# led4.net
KiCad netlist of a schematic drawn in Altium Designer
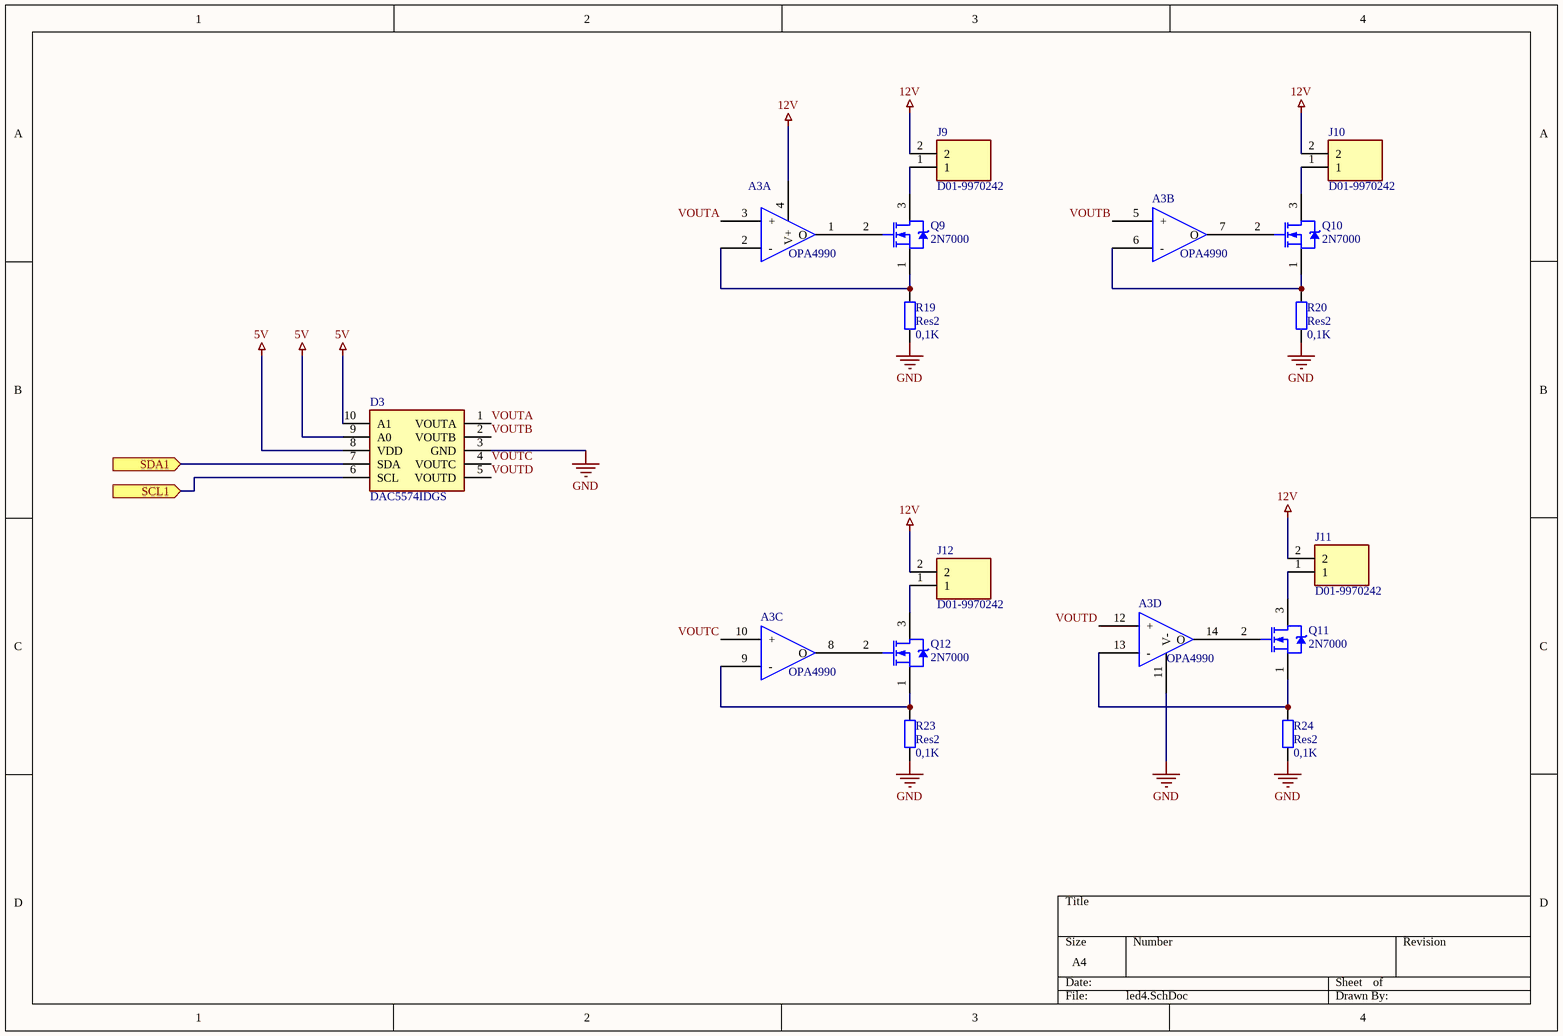
[diagram p0: led4.SchDoc]

(export (version "E")
  (design (tool "Eeschema 10.0.6"))
  (components
    (comp (ref "A3")
      (value "OPA4990")
      (footprint "SOIC127P600X175-14N")
      (libsource (lib "Kalibracija") (part "OPA4990"))
    )
    (comp (ref "D3")
      (value "DAC5574IDGS")
      (footprint "SOP50P490X110-10N")
      (description "Integrated Circuit")
      (fields
        (field (name "MOUSER PART NUMBER") "595-DAC5574IDGS")
        (field (name "RS PART NUMBER") "6621533P")
      )
      (libsource (lib "*") (part "DAC5574IDGS"))
    )
    (comp (ref "J9")
      (value "D01-9970242")
      (footprint "HDR1X2")
      (description "Connector")
      (fields (field (name "MOUSER PART NUMBER") "855-D01-9970242"))
      (libsource (lib "SamacSys2") (part "D01-9970242"))
    )
    (comp (ref "J10")
      (value "D01-9970242")
      (footprint "HDR1X2")
      (description "Connector")
      (fields (field (name "MOUSER PART NUMBER") "855-D01-9970242"))
      (libsource (lib "SamacSys2") (part "D01-9970242"))
    )
    (comp (ref "J11")
      (value "D01-9970242")
      (footprint "HDR1X2")
      (description "Connector")
      (fields (field (name "MOUSER PART NUMBER") "855-D01-9970242"))
      (libsource (lib "SamacSys2") (part "D01-9970242"))
    )
    (comp (ref "J12")
      (value "D01-9970242")
      (footprint "HDR1X2")
      (description "Connector")
      (fields (field (name "MOUSER PART NUMBER") "855-D01-9970242"))
      (libsource (lib "SamacSys2") (part "D01-9970242"))
    )
    (comp (ref "Q9")
      (value "2N7000")
      (footprint "ONSC-TO-92-3-29-11")
      (description "Small Signal MOSFET, 200 mA, 60 V, N-Channel, 3-Pin TO-92, Bulk Box")
      (fields (field (name "MANUFACTURER") "On Semiconductor"))
      (libsource (lib "Components - 24.04.20 - 07.58") (part "CMP-1058-00936-1"))
    )
    (comp (ref "Q10")
      (value "2N7000")
      (footprint "ONSC-TO-92-3-29-11")
      (description "Small Signal MOSFET, 200 mA, 60 V, N-Channel, 3-Pin TO-92, Bulk Box")
      (fields (field (name "MANUFACTURER") "On Semiconductor"))
      (libsource (lib "Components - 24.04.20 - 07.58") (part "CMP-1058-00936-1"))
    )
    (comp (ref "Q11")
      (value "2N7000")
      (footprint "ONSC-TO-92-3-29-11")
      (description "Small Signal MOSFET, 200 mA, 60 V, N-Channel, 3-Pin TO-92, Bulk Box")
      (fields (field (name "MANUFACTURER") "On Semiconductor"))
      (libsource (lib "Components - 24.04.20 - 07.58") (part "CMP-1058-00936-1"))
    )
    (comp (ref "Q12")
      (value "2N7000")
      (footprint "ONSC-TO-92-3-29-11")
      (description "Small Signal MOSFET, 200 mA, 60 V, N-Channel, 3-Pin TO-92, Bulk Box")
      (fields (field (name "MANUFACTURER") "On Semiconductor"))
      (libsource (lib "Components - 24.04.20 - 07.58") (part "CMP-1058-00936-1"))
    )
    (comp (ref "R19")
      (value "Res2")
      (footprint "C1210")
      (description "Resistor")
      (fields (field (name "ALTIUM_VALUE") "0,1K") (field (name "PUBLISHER") "Altium Limited"))
      (libsource (lib "Miscellaneous Devices") (part "Res2"))
    )
    (comp (ref "R20")
      (value "Res2")
      (footprint "C1210")
      (description "Resistor")
      (fields (field (name "ALTIUM_VALUE") "0,1K") (field (name "PUBLISHER") "Altium Limited"))
      (libsource (lib "Miscellaneous Devices") (part "Res2"))
    )
    (comp (ref "R23")
      (value "Res2")
      (footprint "C1210")
      (description "Resistor")
      (fields (field (name "ALTIUM_VALUE") "0,1K") (field (name "PUBLISHER") "Altium Limited"))
      (libsource (lib "Miscellaneous Devices") (part "Res2"))
    )
    (comp (ref "R24")
      (value "Res2")
      (footprint "C1210")
      (description "Resistor")
      (fields (field (name "ALTIUM_VALUE") "0,1K") (field (name "PUBLISHER") "Altium Limited"))
      (libsource (lib "Miscellaneous Devices") (part "Res2"))
    )
  )
  (nets
    (net (code "1") (name "/SCL1") (class "Default")
      (node (ref "D3") (pin "6") (pinfunction "SCL_6") (pintype "passive"))
    )
    (net (code "2") (name "/SDA1") (class "Default")
      (node (ref "D3") (pin "7") (pinfunction "SDA_7") (pintype "passive"))
    )
    (net (code "3") (name "/VOUTA") (class "Default")
      (node (ref "A3") (pin "3") (pinfunction "+_3") (pintype "passive"))
      (node (ref "D3") (pin "1") (pinfunction "VOUTA_1") (pintype "passive"))
    )
    (net (code "4") (name "/VOUTB") (class "Default")
      (node (ref "A3") (pin "5") (pinfunction "+_5") (pintype "passive"))
      (node (ref "D3") (pin "2") (pinfunction "VOUTB_2") (pintype "passive"))
    )
    (net (code "5") (name "/VOUTC") (class "Default")
      (node (ref "A3") (pin "10") (pinfunction "+_10") (pintype "passive"))
      (node (ref "D3") (pin "4") (pinfunction "VOUTC_4") (pintype "passive"))
    )
    (net (code "6") (name "/VOUTD") (class "Default")
      (node (ref "A3") (pin "12") (pinfunction "+_12") (pintype "passive"))
      (node (ref "D3") (pin "5") (pinfunction "VOUTD_5") (pintype "passive"))
    )
    (net (code "7") (name "5V") (class "Default")
      (node (ref "D3") (pin "10") (pinfunction "A1_10") (pintype "passive"))
      (node (ref "D3") (pin "8") (pinfunction "VDD_8") (pintype "passive"))
      (node (ref "D3") (pin "9") (pinfunction "A0_9") (pintype "passive"))
    )
    (net (code "8") (name "12V") (class "Default")
      (node (ref "A3") (pin "4") (pinfunction "V+_4") (pintype "power_in"))
      (node (ref "J10") (pin "2") (pinfunction "2_2") (pintype "passive"))
      (node (ref "J11") (pin "2") (pinfunction "2_2") (pintype "passive"))
      (node (ref "J12") (pin "2") (pinfunction "2_2") (pintype "passive"))
      (node (ref "J9") (pin "2") (pinfunction "2_2") (pintype "passive"))
    )
    (net (code "9") (name "GND") (class "Default")
      (node (ref "A3") (pin "11") (pinfunction "V-_11") (pintype "power_in"))
      (node (ref "D3") (pin "3") (pinfunction "GND_3") (pintype "passive"))
      (node (ref "R19") (pin "1") (pinfunction "1_1") (pintype "passive"))
      (node (ref "R20") (pin "1") (pinfunction "1_1") (pintype "passive"))
      (node (ref "R23") (pin "1") (pinfunction "1_1") (pintype "passive"))
      (node (ref "R24") (pin "1") (pinfunction "1_1") (pintype "passive"))
    )
    (net (code "10") (name "Net-(A3A--)") (class "Default")
      (node (ref "A3") (pin "2") (pinfunction "-_2") (pintype "passive"))
      (node (ref "Q9") (pin "1") (pinfunction "S_1") (pintype "passive"))
      (node (ref "R19") (pin "2") (pinfunction "2_2") (pintype "passive"))
    )
    (net (code "11") (name "Net-(A3A-O)") (class "Default")
      (node (ref "A3") (pin "1") (pinfunction "O_1") (pintype "passive"))
      (node (ref "Q9") (pin "2") (pinfunction "G_2") (pintype "passive"))
    )
    (net (code "12") (name "Net-(A3B--)") (class "Default")
      (node (ref "A3") (pin "6") (pinfunction "-_6") (pintype "passive"))
      (node (ref "Q10") (pin "1") (pinfunction "S_1") (pintype "passive"))
      (node (ref "R20") (pin "2") (pinfunction "2_2") (pintype "passive"))
    )
    (net (code "13") (name "Net-(A3B-O)") (class "Default")
      (node (ref "A3") (pin "7") (pinfunction "O_7") (pintype "passive"))
      (node (ref "Q10") (pin "2") (pinfunction "G_2") (pintype "passive"))
    )
    (net (code "14") (name "Net-(A3C--)") (class "Default")
      (node (ref "A3") (pin "9") (pinfunction "-_9") (pintype "passive"))
      (node (ref "Q12") (pin "1") (pinfunction "S_1") (pintype "passive"))
      (node (ref "R23") (pin "2") (pinfunction "2_2") (pintype "passive"))
    )
    (net (code "15") (name "Net-(A3C-O)") (class "Default")
      (node (ref "A3") (pin "8") (pinfunction "O_8") (pintype "passive"))
      (node (ref "Q12") (pin "2") (pinfunction "G_2") (pintype "passive"))
    )
    (net (code "16") (name "Net-(A3D--)") (class "Default")
      (node (ref "A3") (pin "13") (pinfunction "-_13") (pintype "passive"))
      (node (ref "Q11") (pin "1") (pinfunction "S_1") (pintype "passive"))
      (node (ref "R24") (pin "2") (pinfunction "2_2") (pintype "passive"))
    )
    (net (code "17") (name "Net-(A3D-O)") (class "Default")
      (node (ref "A3") (pin "14") (pinfunction "O_14") (pintype "passive"))
      (node (ref "Q11") (pin "2") (pinfunction "G_2") (pintype "passive"))
    )
    (net (code "18") (name "Net-(Q9-D)") (class "Default")
      (node (ref "J9") (pin "1") (pinfunction "1_1") (pintype "passive"))
      (node (ref "Q9") (pin "3") (pinfunction "D_3") (pintype "passive"))
    )
    (net (code "19") (name "Net-(Q10-D)") (class "Default")
      (node (ref "J10") (pin "1") (pinfunction "1_1") (pintype "passive"))
      (node (ref "Q10") (pin "3") (pinfunction "D_3") (pintype "passive"))
    )
    (net (code "20") (name "Net-(Q11-D)") (class "Default")
      (node (ref "J11") (pin "1") (pinfunction "1_1") (pintype "passive"))
      (node (ref "Q11") (pin "3") (pinfunction "D_3") (pintype "passive"))
    )
    (net (code "21") (name "Net-(Q12-D)") (class "Default")
      (node (ref "J12") (pin "1") (pinfunction "1_1") (pintype "passive"))
      (node (ref "Q12") (pin "3") (pinfunction "D_3") (pintype "passive"))
    )
  )
)
